# GSM_On-Off_Signal_Control.net
KiCad netlist of a schematic drawn in Altium Designer
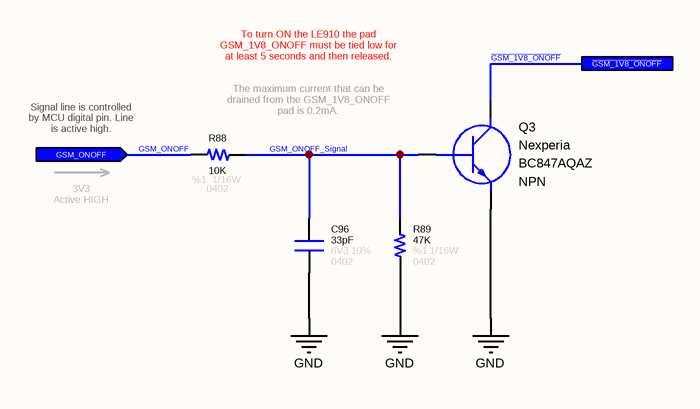
[diagram p0: GSM On-Off Signal Control.SchDoc]

(export (version "E")
  (design (tool "Eeschema 10.0.6"))
  (components
    (comp (ref "C96")
      (value "33pF")
      (footprint "CAPACITOR_0402")
      (description "Capacitor - 33pF [0402] (Ceramic)")
      (fields
        (field (name "MANUFACTURER PART NUMBER") "C0402C330J9RACAUTO")
        (field (name "TOLERANCE") "10%")
        (field (name "CASE") "0402")
        (field (name "VOLTAGE") "6V3")
      )
      (libsource (lib "Akkoyun") (part "Capacitor - 33pF [0402-6V3]"))
    )
    (comp (ref "Q3")
      (value "BC847AQAZ")
      (footprint "SOT1215")
      (description "Bipolar NPN Transistors")
      (fields
        (field (name "MANUFACTURER NAME") "Nexperia")
        (field (name "MANUFACTURER PART NUMBER") "BC847AQAZ")
        (field (name "POLARITY") "NPN")
      )
      (libsource (lib "Akkoyun") (part "Transistor - BC847"))
    )
    (comp (ref "R88")
      (value "10K")
      (footprint "RESISTOR_0402")
      (description "Thick Film Resistors - SMD 1/16 W 10 KOhm 1%")
      (fields
        (field (name "MANUFACTURER PART NUMBER") "CRCW040210K0FKED")
        (field (name "TOLERANCE") "%1")
        (field (name "CASE") "0402")
        (field (name "POWER") "1/16W")
        (field (name "Comment") "10K - 0402 - %1 - 1/16W")
      )
      (libsource (lib "Akkoyun") (part "Resistor - 10K [0402]"))
    )
    (comp (ref "R89")
      (value "47K")
      (footprint "RESISTOR_0402")
      (description "Thick Film Resistors - SMD 1/16 W 47 KOhm 1%")
      (fields
        (field (name "MANUFACTURER PART NUMBER") "CRCW040247K0FKED")
        (field (name "TOLERANCE") "%1")
        (field (name "CASE") "0402")
        (field (name "POWER") "1/16W")
        (field (name "Comment") "47K - 0402 - %1 - 1/16W")
      )
      (libsource (lib "Akkoyun") (part "Resistor - 47K [0402]"))
    )
  )
  (nets
    (net (code "1") (name "/GSM_ONOFF") (class "Default")
      (node (ref "R88") (pin "2") (pinfunction "2_2") (pintype "passive"))
    )
    (net (code "2") (name "/GSM_ONOFF_Signal") (class "Default")
      (node (ref "C96") (pin "2") (pinfunction "2_2") (pintype "passive"))
      (node (ref "Q3") (pin "1") (pinfunction "B_1") (pintype "passive"))
      (node (ref "R88") (pin "1") (pinfunction "1_1") (pintype "passive"))
      (node (ref "R89") (pin "2") (pinfunction "2_2") (pintype "passive"))
    )
    (net (code "3") (name "/~{GSM_1V8_ONOFF}") (class "Default")
      (node (ref "Q3") (pin "3") (pinfunction "C_3") (pintype "passive"))
    )
    (net (code "4") (name "GND") (class "Default")
      (node (ref "C96") (pin "1") (pinfunction "1_1") (pintype "passive"))
      (node (ref "Q3") (pin "2") (pinfunction "E_2") (pintype "passive"))
      (node (ref "R89") (pin "1") (pinfunction "1_1") (pintype "passive"))
    )
  )
)
